# Power_Stage.net
KiCad netlist of a schematic drawn in Altium Designer
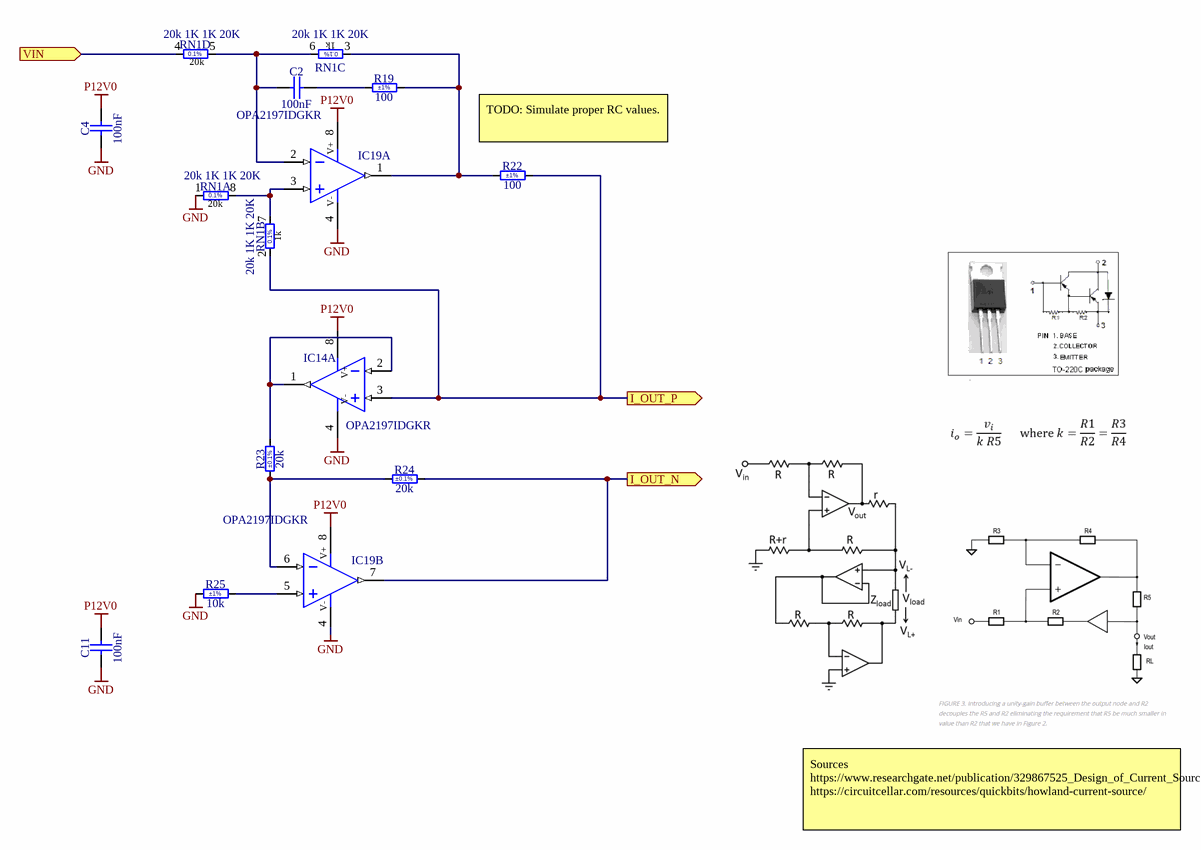
[diagram p0: Power_Stage.SchDoc]

(export (version "E")
  (design (tool "Eeschema 10.0.6"))
  (components
    (comp (ref "C2")
      (value "100nF")
      (footprint "CAPC1005X55N")
      (description "Non-polarised capacitor")
      (fields
        (field (name "PART NUMBER") "CC0402_100NF_16V_10%_X5R")
        (field (name "VOLTAGE") "16V")
        (field (name "AUTHOR") "CERN DEM JLC")
      )
      (libsource (lib "Capacitors") (part "Capacitor - non polarized"))
    )
    (comp (ref "C4")
      (value "100nF")
      (footprint "CAPC1005X55N")
      (description "Non-polarised capacitor")
      (fields
        (field (name "PART NUMBER") "CC0402_100NF_16V_10%_X5R")
        (field (name "VOLTAGE") "16V")
        (field (name "AUTHOR") "CERN DEM JLC")
      )
      (libsource (lib "Capacitors") (part "Capacitor - non polarized"))
    )
    (comp (ref "C11")
      (value "100nF")
      (footprint "CAPC1005X55N")
      (description "Non-polarised capacitor")
      (fields
        (field (name "PART NUMBER") "CC0402_100NF_16V_10%_X5R")
        (field (name "VOLTAGE") "16V")
        (field (name "AUTHOR") "CERN DEM JLC")
      )
      (libsource (lib "Capacitors") (part "Capacitor - non polarized"))
    )
    (comp (ref "IC14")
      (value "OPA2197IDGKR")
      (footprint "SOP65P490X110-8N")
      (description "36-V, Precision, Rail-to-Rail Input Output, Low Offset Voltage Op Amp 8-VSSOP")
      (fields (field (name "MANUFACTURER") "TEXAS INSTRUMENTS") (field (name "AUTHOR") "GK"))
      (libsource (lib "ICs_Analog_Interfaces") (part "OA_OPA2197IDGKR"))
    )
    (comp (ref "IC19")
      (value "OPA2197IDGKR")
      (footprint "SOP65P490X110-8N")
      (description "36-V, Precision, Rail-to-Rail Input Output, Low Offset Voltage Op Amp 8-VSSOP")
      (fields (field (name "MANUFACTURER") "TEXAS INSTRUMENTS") (field (name "AUTHOR") "GK"))
      (libsource (lib "ICs_Analog_Interfaces") (part "OA_OPA2197IDGKR"))
    )
    (comp (ref "R19")
      (value "100")
      (footprint "RESC1608X55N")
      (description "Resistor - 1%")
      (fields
        (field (name "TOLERANCE") "±1%")
        (field (name "PART NUMBER") "R0603_100R_1%_0.1W_100PPM")
        (field (name "POWER") "0.1W")
        (field (name "AUTHOR") "CERN DEM JLC")
      )
      (libsource (lib "Resistors") (part "Resistor - 1%"))
    )
    (comp (ref "R22")
      (value "100")
      (footprint "RESC1608X55N")
      (description "Resistor - 1%")
      (fields
        (field (name "TOLERANCE") "±1%")
        (field (name "PART NUMBER") "R0603_100R_1%_0.1W_100PPM")
        (field (name "POWER") "0.1W")
        (field (name "AUTHOR") "CERN DEM JLC")
      )
      (libsource (lib "Resistors") (part "Resistor - 1%"))
    )
    (comp (ref "R23")
      (value "20k")
      (footprint "RESC1608X55N")
      (description "Resistor - 0.1%")
      (fields
        (field (name "TOLERANCE") "±0.1%")
        (field (name "PART NUMBER") "R0603_20K_0.1%_0.063W_10PPM")
        (field (name "POWER") "0.063W")
        (field (name "AUTHOR") "CERN DEM JLC")
      )
      (libsource (lib "Resistors") (part "Resistor - 0.1%"))
    )
    (comp (ref "R24")
      (value "20k")
      (footprint "RESC1608X55N")
      (description "Resistor - 0.1%")
      (fields
        (field (name "TOLERANCE") "±0.1%")
        (field (name "PART NUMBER") "R0603_20K_0.1%_0.063W_10PPM")
        (field (name "POWER") "0.063W")
        (field (name "AUTHOR") "CERN DEM JLC")
      )
      (libsource (lib "Resistors") (part "Resistor - 0.1%"))
    )
    (comp (ref "R25")
      (value "10k")
      (footprint "RESC1005X40N")
      (description "Resistor - 1%")
      (fields
        (field (name "TOLERANCE") "±1%")
        (field (name "PART NUMBER") "R0402_10K_1%_0.0625W_100PPM")
        (field (name "POWER") "0.0625W")
        (field (name "AUTHOR") "CERN DEM JLC")
      )
      (libsource (lib "Resistors") (part "Resistor - 1%"))
    )
    (comp (ref "RN1")
      (value "20k 1K 1K 20K")
      (footprint "SOIC127P600X175-8N")
      (description "DIL8 Resistor Network 4 Resistors 4xR 10k-1k-1k-10k 0.1%")
      (fields
        (field (name "PART NUMBER") "RN_20K_1K_VISHAY_AORN10-1A")
        (field (name "POWER") "4x0.1W")
        (field (name "AUTHOR") "GK")
      )
      (libsource (lib "Passives_RC") (part "RN_20K_1K_VISHAY_AORN20-1A"))
    )
  )
  (nets
    (net (code "1") (name "/I_OUT_N") (class "Default")
      (node (ref "IC19") (pin "7") (pinfunction "OUT_7") (pintype "output"))
      (node (ref "R24") (pin "2") (pinfunction "2_2") (pintype "passive"))
    )
    (net (code "2") (name "/I_OUT_P") (class "Default")
      (node (ref "IC14") (pin "3") (pinfunction "IN+_3") (pintype "input"))
      (node (ref "R22") (pin "2") (pinfunction "2_2") (pintype "passive"))
      (node (ref "RN1") (pin "2") (pinfunction "2_2") (pintype "passive"))
    )
    (net (code "3") (name "/VIN") (class "Default")
      (node (ref "RN1") (pin "4") (pinfunction "4_4") (pintype "passive"))
    )
    (net (code "4") (name "GND") (class "Default")
      (node (ref "C11") (pin "1") (pinfunction "1_1") (pintype "passive"))
      (node (ref "C4") (pin "1") (pinfunction "1_1") (pintype "passive"))
      (node (ref "IC14") (pin "4") (pinfunction "V-_4") (pintype "power_in"))
      (node (ref "IC19") (pin "4") (pinfunction "V-_4") (pintype "power_in"))
      (node (ref "R25") (pin "1") (pinfunction "1_1") (pintype "passive"))
      (node (ref "RN1") (pin "1") (pinfunction "1_1") (pintype "passive"))
    )
    (net (code "5") (name "Net-(C2-Pad2)") (class "Default")
      (node (ref "C2") (pin "2") (pinfunction "2_2") (pintype "passive"))
      (node (ref "R19") (pin "1") (pinfunction "1_1") (pintype "passive"))
    )
    (net (code "6") (name "Net-(IC14A-IN-)") (class "Default")
      (node (ref "IC14") (pin "1") (pinfunction "OUT_1") (pintype "output"))
      (node (ref "IC14") (pin "2") (pinfunction "IN-_2") (pintype "input"))
      (node (ref "R23") (pin "2") (pinfunction "2_2") (pintype "passive"))
    )
    (net (code "7") (name "Net-(IC19A-IN+)") (class "Default")
      (node (ref "IC19") (pin "3") (pinfunction "IN+_3") (pintype "input"))
      (node (ref "RN1") (pin "7") (pinfunction "7_7") (pintype "passive"))
      (node (ref "RN1") (pin "8") (pinfunction "8_8") (pintype "passive"))
    )
    (net (code "8") (name "Net-(IC19A-IN-)") (class "Default")
      (node (ref "C2") (pin "1") (pinfunction "1_1") (pintype "passive"))
      (node (ref "IC19") (pin "2") (pinfunction "IN-_2") (pintype "input"))
      (node (ref "RN1") (pin "5") (pinfunction "5_5") (pintype "passive"))
      (node (ref "RN1") (pin "6") (pinfunction "6_6") (pintype "passive"))
    )
    (net (code "9") (name "Net-(IC19A-OUT)") (class "Default")
      (node (ref "IC19") (pin "1") (pinfunction "OUT_1") (pintype "output"))
      (node (ref "R19") (pin "2") (pinfunction "2_2") (pintype "passive"))
      (node (ref "R22") (pin "1") (pinfunction "1_1") (pintype "passive"))
      (node (ref "RN1") (pin "3") (pinfunction "3_3") (pintype "passive"))
    )
    (net (code "10") (name "Net-(IC19B-IN+)") (class "Default")
      (node (ref "IC19") (pin "5") (pinfunction "IN+_5") (pintype "input"))
      (node (ref "R25") (pin "2") (pinfunction "2_2") (pintype "passive"))
    )
    (net (code "11") (name "Net-(IC19B-IN-)") (class "Default")
      (node (ref "IC19") (pin "6") (pinfunction "IN-_6") (pintype "input"))
      (node (ref "R23") (pin "1") (pinfunction "1_1") (pintype "passive"))
      (node (ref "R24") (pin "1") (pinfunction "1_1") (pintype "passive"))
    )
    (net (code "12") (name "P12V0") (class "Default")
      (node (ref "C11") (pin "2") (pinfunction "2_2") (pintype "passive"))
      (node (ref "C4") (pin "2") (pinfunction "2_2") (pintype "passive"))
      (node (ref "IC14") (pin "8") (pinfunction "V+_8") (pintype "power_in"))
      (node (ref "IC19") (pin "8") (pinfunction "V+_8") (pintype "power_in"))
    )
  )
)
